# 03_Display.net
KiCad netlist of a schematic drawn in Altium Designer
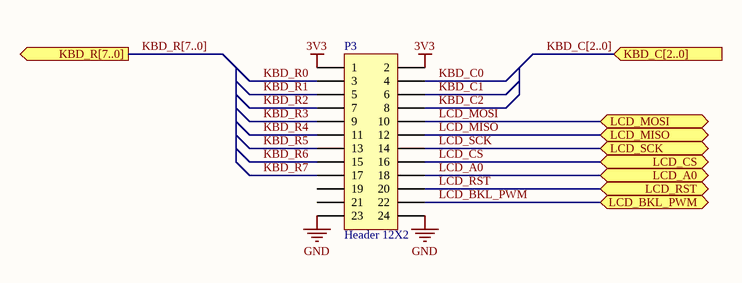
[diagram p0: [03] Display.SchDoc]

(export (version "E")
  (design (tool "Eeschema 10.0.6"))
  (components
    (comp (ref "P3")
      (value "Header 12X2")
      (footprint "HDR2X12")
      (description "Header, 12-Pin, Dual row")
      (fields (field (name "PUBLISHER") "Altium Limited"))
      (libsource (lib "Miscellaneous Connectors") (part "Header 12X2"))
    )
  )
  (nets
    (net (code "1") (name "/KBD_C0") (class "Default")
      (node (ref "P3") (pin "4") (pinfunction "4_4") (pintype "passive"))
    )
    (net (code "2") (name "/KBD_C1") (class "Default")
      (node (ref "P3") (pin "6") (pinfunction "6_6") (pintype "passive"))
    )
    (net (code "3") (name "/KBD_C2") (class "Default")
      (node (ref "P3") (pin "8") (pinfunction "8_8") (pintype "passive"))
    )
    (net (code "5") (name "/KBD_R0") (class "Default")
      (node (ref "P3") (pin "3") (pinfunction "3_3") (pintype "passive"))
    )
    (net (code "6") (name "/KBD_R1") (class "Default")
      (node (ref "P3") (pin "5") (pinfunction "5_5") (pintype "passive"))
    )
    (net (code "7") (name "/KBD_R2") (class "Default")
      (node (ref "P3") (pin "7") (pinfunction "7_7") (pintype "passive"))
    )
    (net (code "8") (name "/KBD_R3") (class "Default")
      (node (ref "P3") (pin "9") (pinfunction "9_9") (pintype "passive"))
    )
    (net (code "9") (name "/KBD_R4") (class "Default")
      (node (ref "P3") (pin "11") (pinfunction "11_11") (pintype "passive"))
    )
    (net (code "10") (name "/KBD_R5") (class "Default")
      (node (ref "P3") (pin "13") (pinfunction "13_13") (pintype "passive"))
    )
    (net (code "11") (name "/KBD_R6") (class "Default")
      (node (ref "P3") (pin "15") (pinfunction "15_15") (pintype "passive"))
    )
    (net (code "12") (name "/KBD_R7") (class "Default")
      (node (ref "P3") (pin "17") (pinfunction "17_17") (pintype "passive"))
    )
    (net (code "14") (name "/LCD_A0") (class "Default")
      (node (ref "P3") (pin "18") (pinfunction "18_18") (pintype "passive"))
    )
    (net (code "15") (name "/LCD_BKL_PWM") (class "Default")
      (node (ref "P3") (pin "22") (pinfunction "22_22") (pintype "passive"))
    )
    (net (code "16") (name "/LCD_CS") (class "Default")
      (node (ref "P3") (pin "16") (pinfunction "16_16") (pintype "passive"))
    )
    (net (code "17") (name "/LCD_MISO") (class "Default")
      (node (ref "P3") (pin "12") (pinfunction "12_12") (pintype "passive"))
    )
    (net (code "18") (name "/LCD_MOSI") (class "Default")
      (node (ref "P3") (pin "10") (pinfunction "10_10") (pintype "passive"))
    )
    (net (code "19") (name "/LCD_RST") (class "Default")
      (node (ref "P3") (pin "20") (pinfunction "20_20") (pintype "passive"))
    )
    (net (code "20") (name "/LCD_SCK") (class "Default")
      (node (ref "P3") (pin "14") (pinfunction "14_14") (pintype "passive"))
    )
    (net (code "21") (name "3V3") (class "Default")
      (node (ref "P3") (pin "1") (pinfunction "1_1") (pintype "passive"))
      (node (ref "P3") (pin "2") (pinfunction "2_2") (pintype "passive"))
    )
    (net (code "22") (name "GND") (class "Default")
      (node (ref "P3") (pin "23") (pinfunction "23_23") (pintype "passive"))
      (node (ref "P3") (pin "24") (pinfunction "24_24") (pintype "passive"))
    )
    (net (code "23") (name "unconnected-(P3-Pad19)") (class "Default")
      (node (ref "P3") (pin "19") (pinfunction "19_19") (pintype "passive"))
    )
    (net (code "24") (name "unconnected-(P3-Pad21)") (class "Default")
      (node (ref "P3") (pin "21") (pinfunction "21_21") (pintype "passive"))
    )
  )
)
